# Output_Relay.net
KiCad netlist of a schematic drawn in Altium Designer
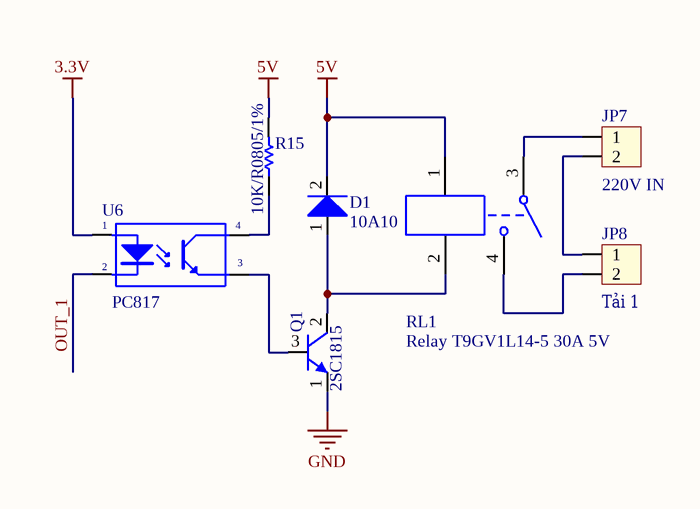
[diagram p0: Output_Relay.SchDoc]

(export (version "E")
  (design (tool "Eeschema 10.0.6"))
  (components
    (comp (ref "D1")
      (value "10A10")
      (footprint "10A10")
      (description "Diode LS 10A 1000V DO-201EX")
      (libsource (lib "lpson") (part "10A10"))
    )
    (comp (ref "JP7")
      (value "220V IN")
      (footprint "DOMINO_OSTTC_2P")
      (description "Connector 2")
      (libsource (lib "lpson") (part "Con2"))
    )
    (comp (ref "JP8")
      (value "Tải 1")
      (footprint "DOMINO_OSTTC_2P")
      (description "Connector 2")
      (libsource (lib "lpson") (part "Con2"))
    )
    (comp (ref "Q1")
      (value "2SC1815")
      (footprint "2SC1815")
      (description "Trans NPN 50V 150mA TO-92")
      (libsource (lib "lpson") (part "2SC1815"))
    )
    (comp (ref "R15")
      (value "10K/R0805/1%")
      (footprint "Res 0805 SMD")
      (description "RES SMD 249K OHM 1% 1/10W 0805")
      (fields
        (field (name "MANUFACTURER") "Yageo")
        (field (name "MANUFACTURER PART NUMBER") "RC0603FR-07249KL")
      )
      (libsource (lib "GSHT_181013") (part "249K/R0805/1%"))
    )
    (comp (ref "RL1")
      (value "Relay T9GV1L14-5 30A 5V")
      (footprint "Relay T9GV1L14-5 30A 5V")
      (description "Single-Pole Dual-Throw Relay")
      (fields (field (name "PUBLISHER") "Altium Limited"))
      (libsource (lib "PCB_ESP32_RFID") (part "Relay T9GV1L14-5 30A 5V"))
    )
    (comp (ref "U6")
      (value "PC817")
      (footprint "PC817")
      (description "Single Opto")
      (libsource (lib "lpson") (part "PC817"))
    )
  )
  (nets
    (net (code "1") (name "/OUT_1") (class "Default")
      (node (ref "U6") (pin "2") (pinfunction "K_2") (pintype "passive"))
    )
    (net (code "2") (name "3.3V") (class "Default")
      (node (ref "U6") (pin "1") (pinfunction "A_1") (pintype "passive"))
    )
    (net (code "3") (name "5V") (class "Default")
      (node (ref "D1") (pin "2") (pinfunction "K_2") (pintype "passive"))
      (node (ref "R15") (pin "2") (pinfunction "2_2") (pintype "passive"))
      (node (ref "RL1") (pin "1") (pinfunction "1_1") (pintype "passive"))
    )
    (net (code "4") (name "GND") (class "Default")
      (node (ref "Q1") (pin "1") (pinfunction "E_1") (pintype "passive"))
    )
    (net (code "5") (name "Net-(D1-A)") (class "Default")
      (node (ref "D1") (pin "1") (pinfunction "A_1") (pintype "passive"))
      (node (ref "Q1") (pin "2") (pinfunction "C_2") (pintype "passive"))
      (node (ref "RL1") (pin "2") (pinfunction "2_2") (pintype "passive"))
    )
    (net (code "6") (name "Net-(JP7-Pad1)") (class "Default")
      (node (ref "JP7") (pin "1") (pinfunction "1_1") (pintype "passive"))
      (node (ref "RL1") (pin "3") (pinfunction "3_3") (pintype "passive"))
    )
    (net (code "7") (name "Net-(JP7-Pad2)") (class "Default")
      (node (ref "JP7") (pin "2") (pinfunction "2_2") (pintype "passive"))
      (node (ref "JP8") (pin "1") (pinfunction "1_1") (pintype "passive"))
    )
    (net (code "8") (name "Net-(JP8-Pad2)") (class "Default")
      (node (ref "JP8") (pin "2") (pinfunction "2_2") (pintype "passive"))
      (node (ref "RL1") (pin "4") (pinfunction "4_4") (pintype "passive"))
    )
    (net (code "9") (name "Net-(Q1-B)") (class "Default")
      (node (ref "Q1") (pin "3") (pinfunction "B_3") (pintype "passive"))
      (node (ref "U6") (pin "3") (pinfunction "E_3") (pintype "passive"))
    )
    (net (code "10") (name "Net-(U6-C)") (class "Default")
      (node (ref "R15") (pin "1") (pinfunction "1_1") (pintype "passive"))
      (node (ref "U6") (pin "4") (pinfunction "C_4") (pintype "passive"))
    )
  )
)
